# SparkFun_HX711_Load_Cell.net
KiCad netlist of a schematic drawn in EAGLE
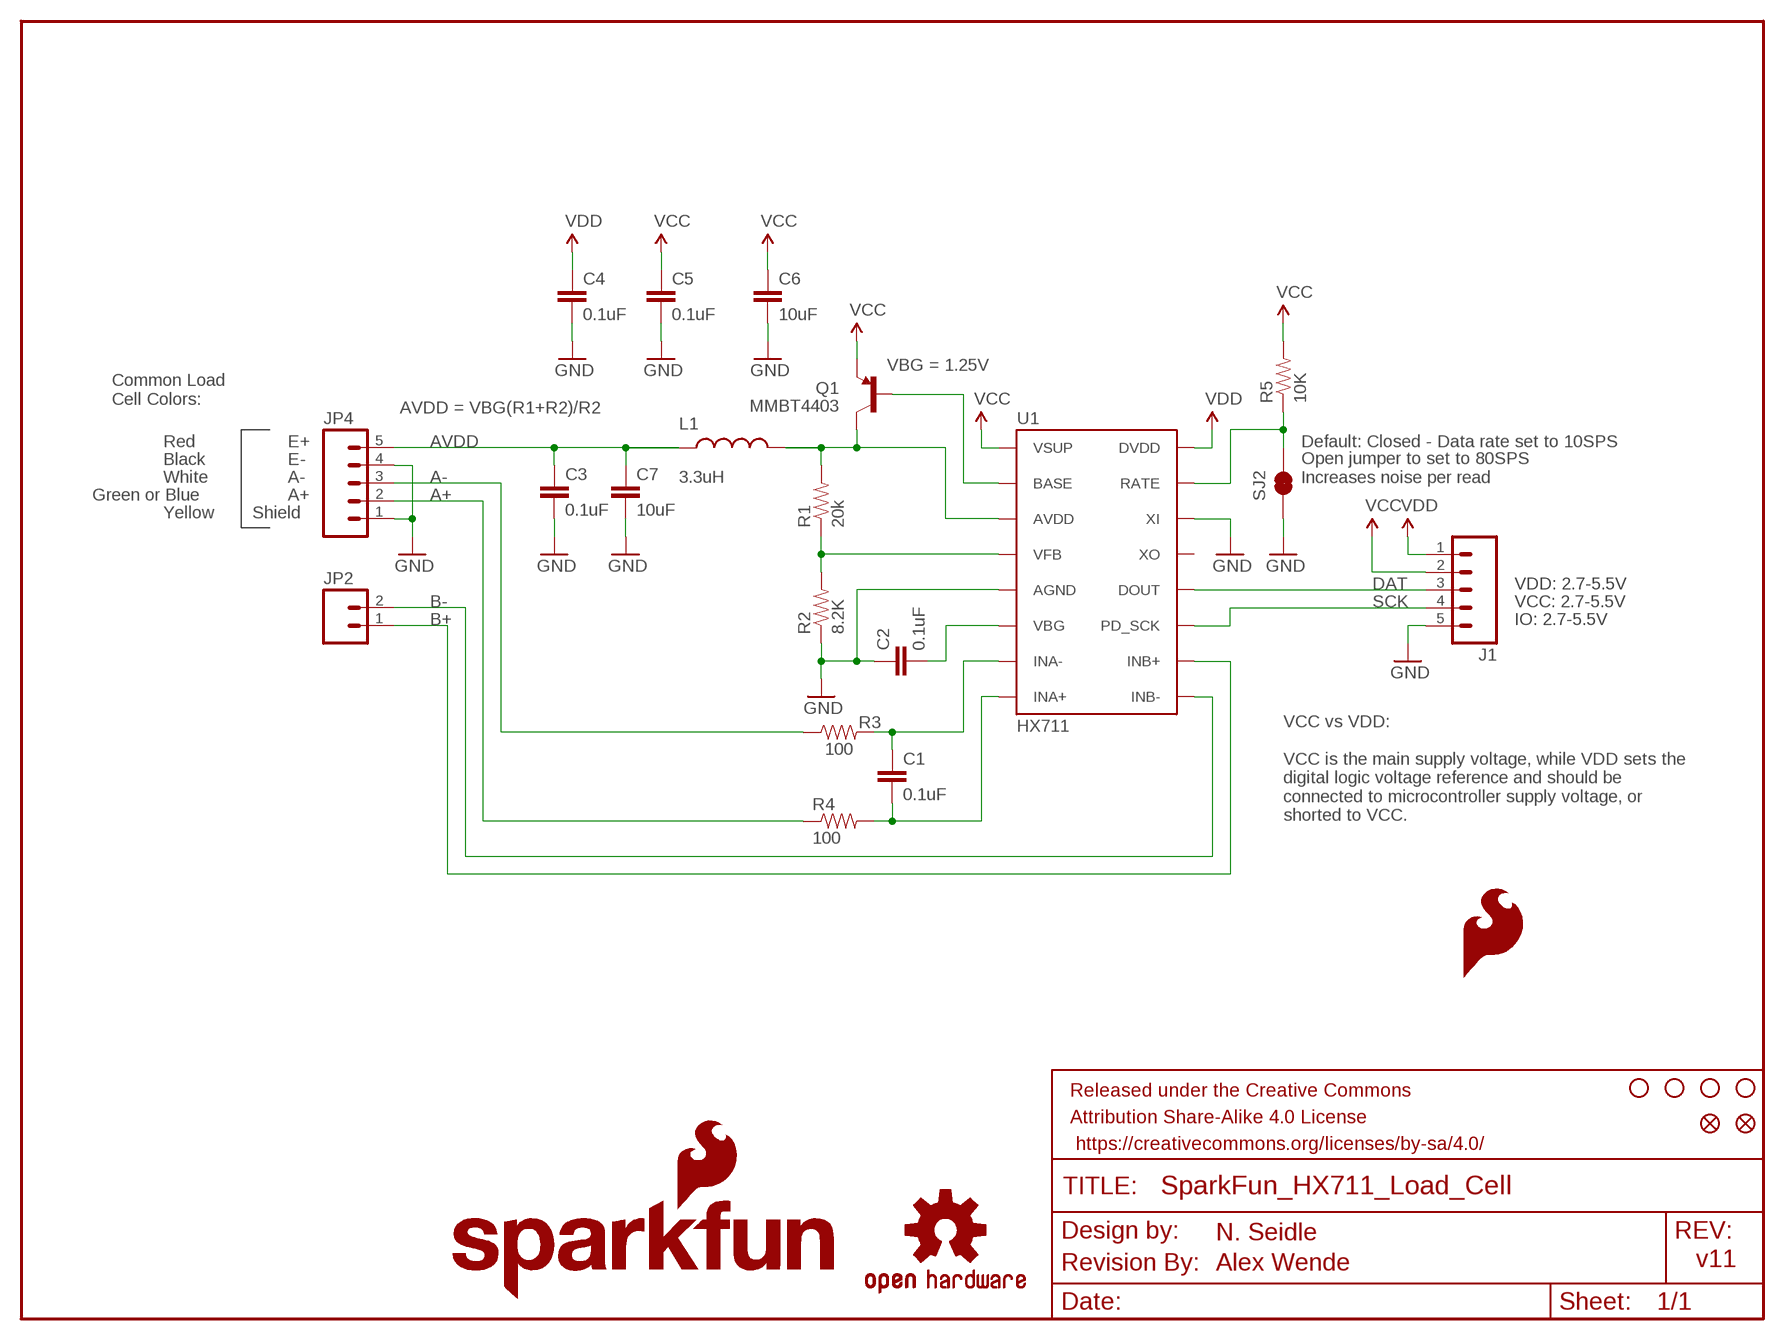
[diagram p0: schematic, sheet 1]

(export (version "E")
  (design (tool "Eeschema 10.0.6"))
  (components
    (comp (ref "C1")
      (value "0.1uF")
      (footprint "eagle-import:0603-CAP")
      (libsource (lib "eagle-import") (part "0.1UF-25V-5%(0603)"))
    )
    (comp (ref "C2")
      (value "0.1uF")
      (footprint "eagle-import:0603-CAP")
      (libsource (lib "eagle-import") (part "0.1UF-25V-5%(0603)"))
    )
    (comp (ref "C3")
      (value "0.1uF")
      (footprint "eagle-import:0603-CAP")
      (libsource (lib "eagle-import") (part "0.1UF-25V-5%(0603)"))
    )
    (comp (ref "C4")
      (value "0.1uF")
      (footprint "eagle-import:0603-CAP")
      (libsource (lib "eagle-import") (part "0.1UF-25V-5%(0603)"))
    )
    (comp (ref "C5")
      (value "0.1uF")
      (footprint "eagle-import:0603-CAP")
      (libsource (lib "eagle-import") (part "0.1UF-25V-5%(0603)"))
    )
    (comp (ref "C6")
      (value "10uF")
      (footprint "eagle-import:1210")
      (libsource (lib "eagle-import") (part "10UF50V20%(1210)"))
    )
    (comp (ref "C7")
      (value "10uF")
      (footprint "eagle-import:1210")
      (libsource (lib "eagle-import") (part "10UF50V20%(1210)"))
    )
    (comp (ref "FID1")
      (value "FIDUCIAL1X2")
      (footprint "eagle-import:FIDUCIAL-1X2")
      (libsource (lib "eagle-import") (part "FIDUCIAL1X2"))
    )
    (comp (ref "FID2")
      (value "FIDUCIAL1X2")
      (footprint "eagle-import:FIDUCIAL-1X2")
      (libsource (lib "eagle-import") (part "FIDUCIAL1X2"))
    )
    (comp (ref "FRAME1")
      (value "FRAME-LETTER")
      (footprint "eagle-import:CREATIVE_COMMONS")
      (libsource (lib "eagle-import") (part "FRAME-LETTER"))
    )
    (comp (ref "J1")
      (value "M05PTH")
      (footprint "eagle-import:1X05")
      (libsource (lib "eagle-import") (part "M05PTH"))
    )
    (comp (ref "JP2")
      (value "M02PTH")
      (footprint "eagle-import:1X02")
      (libsource (lib "eagle-import") (part "M02PTH"))
    )
    (comp (ref "JP4")
      (value "M05PTH")
      (footprint "eagle-import:1X05")
      (libsource (lib "eagle-import") (part "M05PTH"))
    )
    (comp (ref "L1")
      (value "3.3uH")
      (footprint "eagle-import:0805")
      (libsource (lib "eagle-import") (part "INDUCTOR0805-IND"))
    )
    (comp (ref "LOGO1")
      (value "SFE_LOGO_NAME_FLAME.1_INCH")
      (footprint "eagle-import:SFE_LOGO_NAME_FLAME_.1")
      (libsource (lib "eagle-import") (part "SFE_LOGO_NAME_FLAME.1_INCH"))
    )
    (comp (ref "LOGO3")
      (value "SFE_LOGO_FLAME.1_INCH")
      (footprint "eagle-import:SFE_LOGO_FLAME_.1")
      (libsource (lib "eagle-import") (part "SFE_LOGO_FLAME.1_INCH"))
    )
    (comp (ref "Q1")
      (value "MMBT4403")
      (footprint "eagle-import:SOT23-3")
      (libsource (lib "eagle-import") (part "TRANSISTOR_PNPMMBT4403"))
    )
    (comp (ref "R1")
      (value "20k")
      (footprint "eagle-import:0603-RES")
      (libsource (lib "eagle-import") (part "20KOHM1/10W1%(0603)"))
    )
    (comp (ref "R2")
      (value "8.2K")
      (footprint "eagle-import:0603-RES")
      (libsource (lib "eagle-import") (part "8.2KOHM-1/10W-5%(0603)"))
    )
    (comp (ref "R3")
      (value "100")
      (footprint "eagle-import:0603-RES")
      (libsource (lib "eagle-import") (part "100OHM-1/10W-1%(0603)"))
    )
    (comp (ref "R4")
      (value "100")
      (footprint "eagle-import:0603-RES")
      (libsource (lib "eagle-import") (part "100OHM-1/10W-1%(0603)"))
    )
    (comp (ref "R5")
      (value "10K")
      (footprint "eagle-import:0603-RES")
      (libsource (lib "eagle-import") (part "10KOHM-1/10W-1%(0603)0603"))
    )
    (comp (ref "SJ2")
      (value "JUMPER-PAD-2-NC_BY_TRACE")
      (footprint "eagle-import:PAD-JUMPER-2-NC_BY_TRACE_YES_SILK")
      (libsource (lib "eagle-import") (part "JUMPER-PAD-2-NC_BY_TRACE"))
    )
    (comp (ref "STANDOFF1")
      (value "STAND-OFF")
      (footprint "eagle-import:STAND-OFF")
      (libsource (lib "eagle-import") (part "STAND-OFF"))
    )
    (comp (ref "STANDOFF2")
      (value "STAND-OFF")
      (footprint "eagle-import:STAND-OFF")
      (libsource (lib "eagle-import") (part "STAND-OFF"))
    )
    (comp (ref "STANDOFF3")
      (value "STAND-OFF")
      (footprint "eagle-import:STAND-OFF")
      (libsource (lib "eagle-import") (part "STAND-OFF"))
    )
    (comp (ref "STANDOFF4")
      (value "STAND-OFF")
      (footprint "eagle-import:STAND-OFF")
      (libsource (lib "eagle-import") (part "STAND-OFF"))
    )
    (comp (ref "U$1")
      (value "REVISION")
      (footprint "eagle-import:REVISION")
      (libsource (lib "eagle-import") (part "REVISION"))
    )
    (comp (ref "U1")
      (value "HX711")
      (footprint "eagle-import:SO16")
      (libsource (lib "eagle-import") (part "HX711HX711"))
    )
    (comp (ref "U7")
      (value "OSHW-LOGOS")
      (footprint "eagle-import:OSHW-LOGO-S")
      (libsource (lib "eagle-import") (part "OSHW-LOGOS"))
    )
  )
  (nets
    (net (code "1") (name "/A+") (class "Default")
      (node (ref "JP4") (pin "2") (pinfunction "2_2") (pintype "passive"))
      (node (ref "R4") (pin "1") (pinfunction "1_1") (pintype "passive"))
    )
    (net (code "2") (name "/A-") (class "Default")
      (node (ref "JP4") (pin "3") (pinfunction "3_3") (pintype "passive"))
      (node (ref "R3") (pin "1") (pinfunction "1_1") (pintype "passive"))
    )
    (net (code "3") (name "/AVDD") (class "Default")
      (node (ref "C3") (pin "1") (pinfunction "1_1") (pintype "passive"))
      (node (ref "C7") (pin "1") (pinfunction "1_1") (pintype "passive"))
      (node (ref "JP4") (pin "5") (pinfunction "5_5") (pintype "passive"))
      (node (ref "L1") (pin "1") (pinfunction "1_1") (pintype "passive"))
    )
    (net (code "4") (name "/B+") (class "Default")
      (node (ref "JP2") (pin "1") (pinfunction "1_1") (pintype "passive"))
      (node (ref "U1") (pin "10") (pinfunction "INB+_10") (pintype "bidirectional"))
    )
    (net (code "5") (name "/B-") (class "Default")
      (node (ref "JP2") (pin "2") (pinfunction "2_2") (pintype "passive"))
      (node (ref "U1") (pin "9") (pinfunction "INB-_9") (pintype "bidirectional"))
    )
    (net (code "6") (name "/DAT") (class "Default")
      (node (ref "J1") (pin "3") (pinfunction "3_3") (pintype "passive"))
      (node (ref "U1") (pin "12") (pinfunction "DOUT_12") (pintype "bidirectional"))
    )
    (net (code "7") (name "/SCK") (class "Default")
      (node (ref "J1") (pin "4") (pinfunction "4_4") (pintype "passive"))
      (node (ref "U1") (pin "11") (pinfunction "PD_SCK_11") (pintype "bidirectional"))
    )
    (net (code "8") (name "GND") (class "Default")
      (node (ref "C2") (pin "1") (pinfunction "1_1") (pintype "passive"))
      (node (ref "C3") (pin "2") (pinfunction "2_2") (pintype "passive"))
      (node (ref "C4") (pin "2") (pinfunction "2_2") (pintype "passive"))
      (node (ref "C5") (pin "2") (pinfunction "2_2") (pintype "passive"))
      (node (ref "C6") (pin "2") (pinfunction "2_2") (pintype "passive"))
      (node (ref "C7") (pin "2") (pinfunction "2_2") (pintype "passive"))
      (node (ref "J1") (pin "5") (pinfunction "5_5") (pintype "passive"))
      (node (ref "JP4") (pin "1") (pinfunction "1_1") (pintype "passive"))
      (node (ref "JP4") (pin "4") (pinfunction "4_4") (pintype "passive"))
      (node (ref "R2") (pin "1") (pinfunction "1_1") (pintype "passive"))
      (node (ref "SJ2") (pin "1") (pinfunction "1_1") (pintype "passive"))
      (node (ref "U1") (pin "14") (pinfunction "XI_14") (pintype "bidirectional"))
      (node (ref "U1") (pin "5") (pinfunction "AGND_5") (pintype "bidirectional"))
    )
    (net (code "9") (name "Net-(Q1-B)") (class "Default")
      (node (ref "Q1") (pin "1") (pinfunction "B_1") (pintype "passive"))
      (node (ref "U1") (pin "2") (pinfunction "BASE_2") (pintype "bidirectional"))
    )
    (net (code "10") (name "Net-(Q1-C)") (class "Default")
      (node (ref "L1") (pin "2") (pinfunction "2_2") (pintype "passive"))
      (node (ref "Q1") (pin "3") (pinfunction "C_3") (pintype "passive"))
      (node (ref "R1") (pin "2") (pinfunction "2_2") (pintype "passive"))
      (node (ref "U1") (pin "3") (pinfunction "AVDD_3") (pintype "bidirectional"))
    )
    (net (code "11") (name "Net-(U1-INA+)") (class "Default")
      (node (ref "C1") (pin "2") (pinfunction "2_2") (pintype "passive"))
      (node (ref "R4") (pin "2") (pinfunction "2_2") (pintype "passive"))
      (node (ref "U1") (pin "8") (pinfunction "INA+_8") (pintype "bidirectional"))
    )
    (net (code "12") (name "Net-(U1-INA-)") (class "Default")
      (node (ref "C1") (pin "1") (pinfunction "1_1") (pintype "passive"))
      (node (ref "R3") (pin "2") (pinfunction "2_2") (pintype "passive"))
      (node (ref "U1") (pin "7") (pinfunction "INA-_7") (pintype "bidirectional"))
    )
    (net (code "13") (name "Net-(U1-RATE)") (class "Default")
      (node (ref "R5") (pin "1") (pinfunction "1_1") (pintype "passive"))
      (node (ref "SJ2") (pin "2") (pinfunction "2_2") (pintype "passive"))
      (node (ref "U1") (pin "15") (pinfunction "RATE_15") (pintype "bidirectional"))
    )
    (net (code "14") (name "Net-(U1-VBG)") (class "Default")
      (node (ref "C2") (pin "2") (pinfunction "2_2") (pintype "passive"))
      (node (ref "U1") (pin "6") (pinfunction "VBG_6") (pintype "bidirectional"))
    )
    (net (code "15") (name "Net-(U1-VFB)") (class "Default")
      (node (ref "R1") (pin "1") (pinfunction "1_1") (pintype "passive"))
      (node (ref "R2") (pin "2") (pinfunction "2_2") (pintype "passive"))
      (node (ref "U1") (pin "4") (pinfunction "VFB_4") (pintype "bidirectional"))
    )
    (net (code "16") (name "VCC") (class "Default")
      (node (ref "C5") (pin "1") (pinfunction "1_1") (pintype "passive"))
      (node (ref "C6") (pin "1") (pinfunction "1_1") (pintype "passive"))
      (node (ref "J1") (pin "2") (pinfunction "2_2") (pintype "passive"))
      (node (ref "Q1") (pin "2") (pinfunction "E_2") (pintype "passive"))
      (node (ref "R5") (pin "2") (pinfunction "2_2") (pintype "passive"))
      (node (ref "U1") (pin "1") (pinfunction "VSUP_1") (pintype "bidirectional"))
    )
    (net (code "17") (name "VDD") (class "Default")
      (node (ref "C4") (pin "1") (pinfunction "1_1") (pintype "passive"))
      (node (ref "J1") (pin "1") (pinfunction "1_1") (pintype "passive"))
      (node (ref "U1") (pin "16") (pinfunction "DVDD_16") (pintype "bidirectional"))
    )
    (net (code "18") (name "unconnected-(U1-XO-Pad13)") (class "Default")
      (node (ref "U1") (pin "13") (pinfunction "XO_13") (pintype "bidirectional"))
    )
  )
)
